# 5v_AC_DC_reg.net
KiCad netlist of a schematic drawn in EAGLE
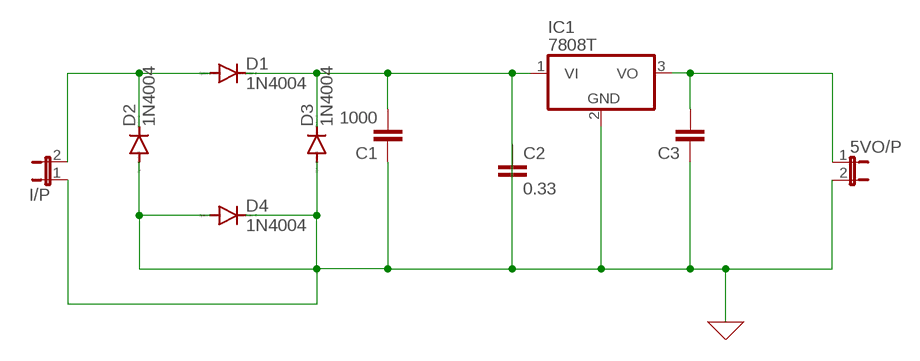
[diagram p0: schematic, sheet 1]

(export (version "E")
  (design (tool "Eeschema 10.0.6"))
  (components
    (comp (ref "5VO/P")
      (value "JP1E")
      (footprint "eagle-import:JP1")
      (libsource (lib "eagle-import") (part "JP1E"))
    )
    (comp (ref "C1")
      (value "1000")
      (footprint "eagle-import:C2.5-3")
      (libsource (lib "eagle-import") (part "C2,5-3"))
    )
    (comp (ref "C2")
      (value "0.33")
      (footprint "eagle-import:C2.5-3")
      (libsource (lib "eagle-import") (part "C2,5-3"))
    )
    (comp (ref "C3")
      (value "C2,5-3")
      (footprint "eagle-import:C2.5-3")
      (libsource (lib "eagle-import") (part "C2,5-3"))
    )
    (comp (ref "D1")
      (value "1N4004")
      (footprint "eagle-import:DO41-10")
      (libsource (lib "eagle-import") (part "1N4004"))
    )
    (comp (ref "D2")
      (value "1N4004")
      (footprint "eagle-import:DO41-10")
      (libsource (lib "eagle-import") (part "1N4004"))
    )
    (comp (ref "D3")
      (value "1N4004")
      (footprint "eagle-import:DO41-10")
      (libsource (lib "eagle-import") (part "1N4004"))
    )
    (comp (ref "D4")
      (value "1N4004")
      (footprint "eagle-import:DO41-10")
      (libsource (lib "eagle-import") (part "1N4004"))
    )
    (comp (ref "I/P")
      (value "JP1E")
      (footprint "eagle-import:JP1")
      (libsource (lib "eagle-import") (part "JP1E"))
    )
    (comp (ref "IC1")
      (value "7808T")
      (footprint "eagle-import:TO220H")
      (libsource (lib "eagle-import") (part "78T08"))
    )
  )
  (nets
    (net (code "1") (name "GND") (class "Default")
      (node (ref "5VO/P") (pin "2") (pinfunction "2_2") (pintype "passive"))
      (node (ref "C1") (pin "1") (pinfunction "1_1") (pintype "passive"))
      (node (ref "C2") (pin "1") (pinfunction "1_1") (pintype "passive"))
      (node (ref "C3") (pin "1") (pinfunction "1_1") (pintype "passive"))
      (node (ref "D2") (pin "A") (pinfunction "A_A") (pintype "passive"))
      (node (ref "D3") (pin "A") (pinfunction "A_A") (pintype "passive"))
      (node (ref "D4") (pin "A") (pinfunction "A_A") (pintype "passive"))
      (node (ref "D4") (pin "C") (pinfunction "C_C") (pintype "passive"))
      (node (ref "I/P") (pin "1") (pinfunction "1_1") (pintype "passive"))
      (node (ref "IC1") (pin "2") (pinfunction "GND_2") (pintype "passive"))
    )
    (net (code "2") (name "Net-(D1-PadA)") (class "Default")
      (node (ref "D1") (pin "A") (pinfunction "A_A") (pintype "passive"))
      (node (ref "D2") (pin "C") (pinfunction "C_C") (pintype "passive"))
      (node (ref "I/P") (pin "2") (pinfunction "2_2") (pintype "passive"))
    )
    (net (code "3") (name "Net-(IC1-VI)") (class "Default")
      (node (ref "C1") (pin "2") (pinfunction "2_2") (pintype "passive"))
      (node (ref "C2") (pin "2") (pinfunction "2_2") (pintype "passive"))
      (node (ref "D1") (pin "C") (pinfunction "C_C") (pintype "passive"))
      (node (ref "D3") (pin "C") (pinfunction "C_C") (pintype "passive"))
      (node (ref "IC1") (pin "1") (pinfunction "VI_1") (pintype "input"))
    )
    (net (code "4") (name "Net-(IC1-VO)") (class "Default")
      (node (ref "5VO/P") (pin "1") (pinfunction "1_1") (pintype "passive"))
      (node (ref "C3") (pin "2") (pinfunction "2_2") (pintype "passive"))
      (node (ref "IC1") (pin "3") (pinfunction "VO_3") (pintype "passive"))
    )
  )
)
